# Modu_control_revD.net
KiCad netlist of a schematic drawn in EAGLE
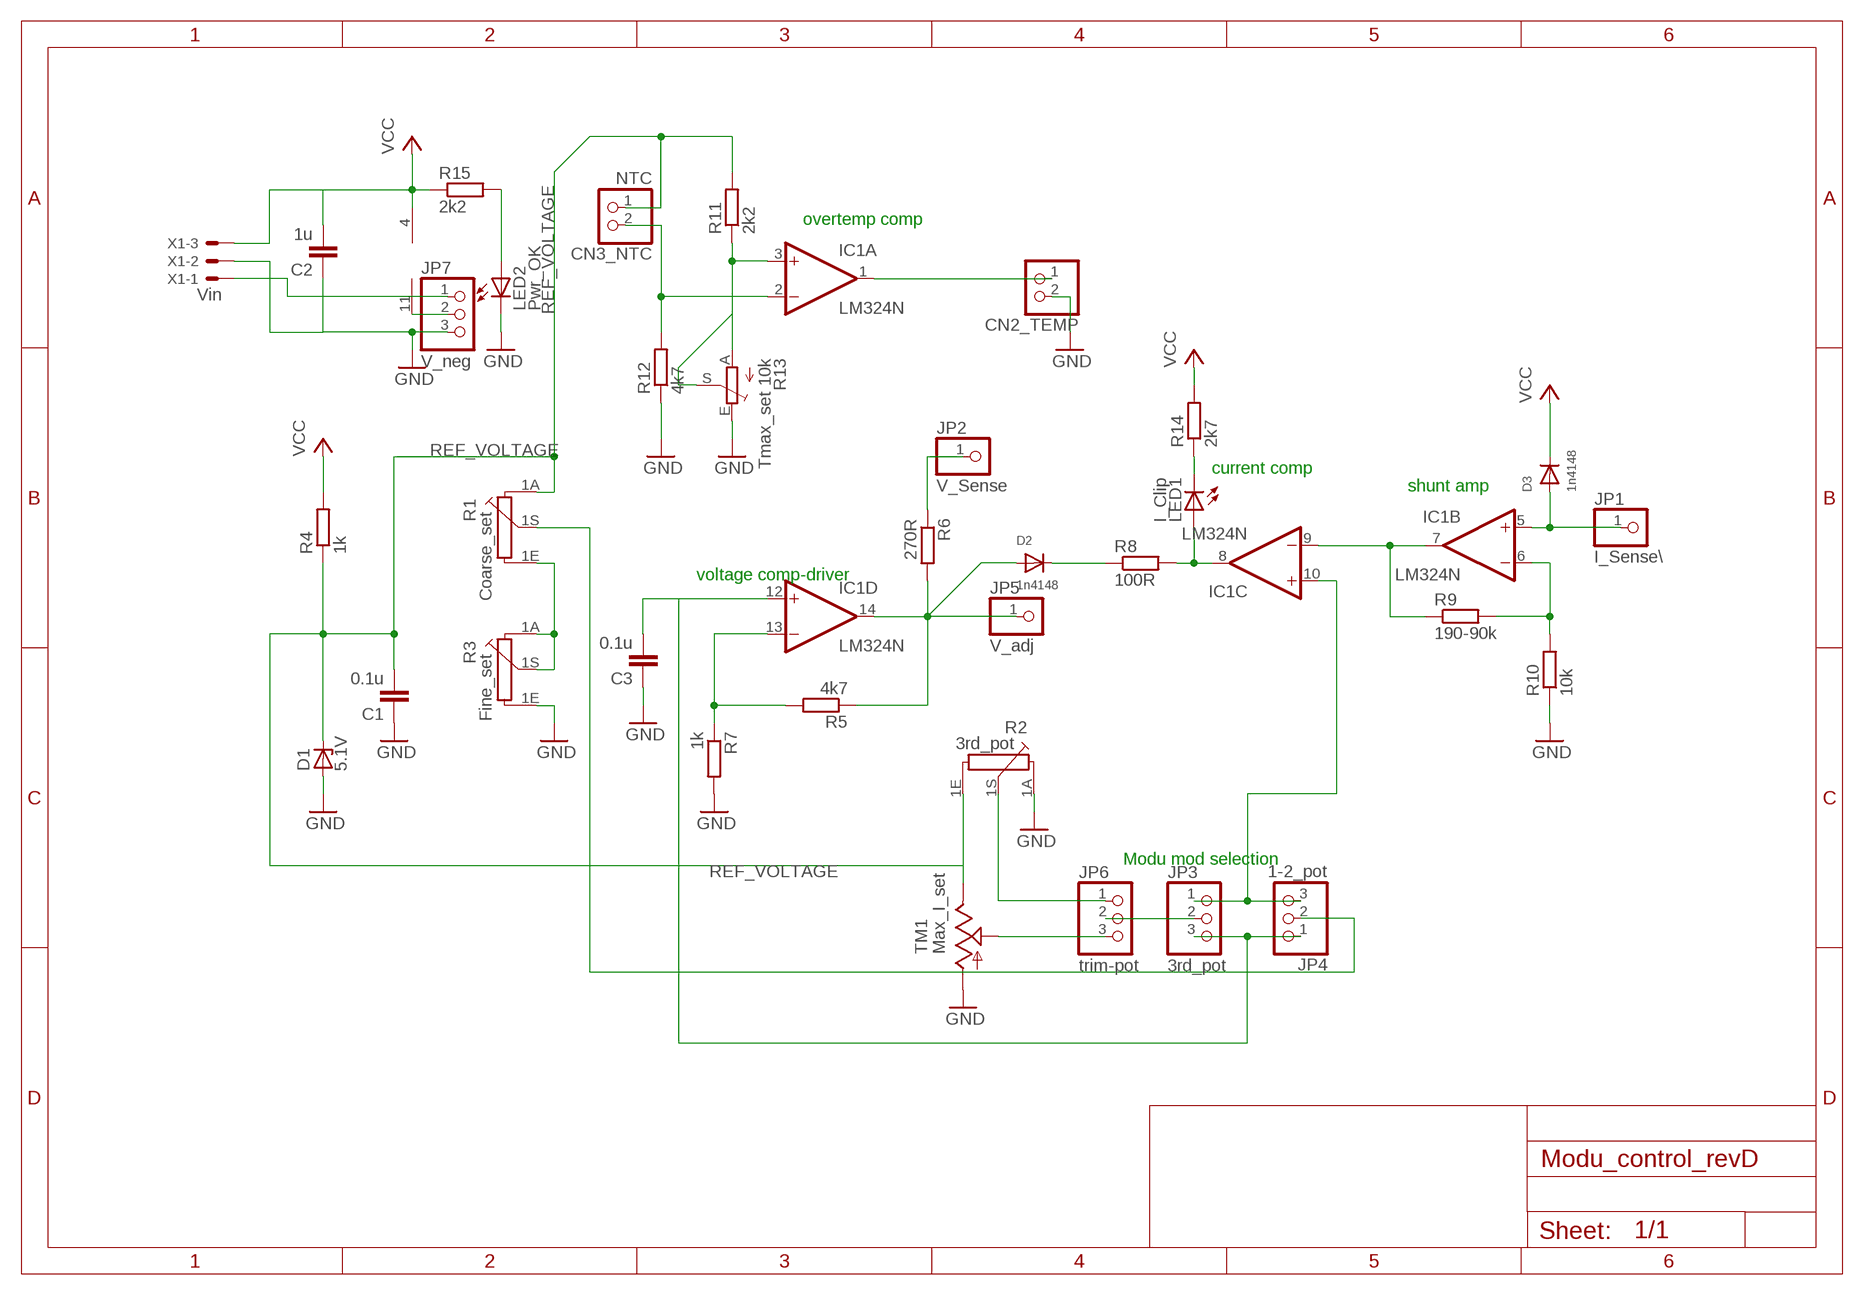
[diagram p0: schematic, sheet 1]

(export (version "E")
  (design (tool "Eeschema 10.0.6"))
  (components
    (comp (ref "C1")
      (value "0.1u")
      (footprint "eagle-import:C050-025X075")
      (libsource (lib "eagle-import") (part "C-EU050-025X075"))
    )
    (comp (ref "C2")
      (value "1u")
      (footprint "eagle-import:C050-025X075")
      (libsource (lib "eagle-import") (part "C-EU050-025X075"))
    )
    (comp (ref "C3")
      (value "0.1u")
      (footprint "eagle-import:C050-025X075")
      (libsource (lib "eagle-import") (part "C-EU050-025X075"))
    )
    (comp (ref "CN2_TEMP")
      (value "JST_2PIN-THM")
      (footprint "eagle-import:JST-PH-2-THM")
      (libsource (lib "eagle-import") (part "JST_2PIN-THM"))
    )
    (comp (ref "CN3_NTC")
      (value "NTC")
      (footprint "eagle-import:JST-PH-2-THM")
      (libsource (lib "eagle-import") (part "JST_2PIN-THM"))
    )
    (comp (ref "D1")
      (value "5.1V")
      (footprint "eagle-import:DO35Z10")
      (libsource (lib "eagle-import") (part "ZENER-DIODEDO35Z10"))
    )
    (comp (ref "D2")
      (value "1n4148")
      (footprint "eagle-import:DO-1N4148")
      (libsource (lib "eagle-import") (part "DIODEDO-1N4148"))
    )
    (comp (ref "D3")
      (value "1n4148")
      (footprint "eagle-import:DO-1N4148")
      (libsource (lib "eagle-import") (part "DIODEDO-1N4148"))
    )
    (comp (ref "IC1")
      (value "LM324N")
      (footprint "eagle-import:DIL14")
      (libsource (lib "eagle-import") (part "LM324N"))
    )
    (comp (ref "JP1")
      (value "I_Sense\\")
      (footprint "eagle-import:1X01")
      (libsource (lib "eagle-import") (part "PINHD-1X1"))
    )
    (comp (ref "JP2")
      (value "V_Sense")
      (footprint "eagle-import:1X01")
      (libsource (lib "eagle-import") (part "PINHD-1X1"))
    )
    (comp (ref "JP3")
      (value "3rd_pot")
      (footprint "eagle-import:1X03")
      (libsource (lib "eagle-import") (part "PINHD-1X3"))
    )
    (comp (ref "JP4")
      (value "1-2_pot")
      (footprint "eagle-import:1X03")
      (libsource (lib "eagle-import") (part "PINHD-1X3"))
    )
    (comp (ref "JP5")
      (value "V_adj")
      (footprint "eagle-import:1X01")
      (libsource (lib "eagle-import") (part "PINHD-1X1"))
    )
    (comp (ref "JP6")
      (value "trim-pot")
      (footprint "eagle-import:1X03")
      (libsource (lib "eagle-import") (part "PINHD-1X3"))
    )
    (comp (ref "JP7")
      (value "V_neg")
      (footprint "eagle-import:1X03")
      (libsource (lib "eagle-import") (part "PINHD-1X3"))
    )
    (comp (ref "LED1")
      (value "I_Clip")
      (footprint "eagle-import:LED3MM")
      (libsource (lib "eagle-import") (part "LED3MM"))
    )
    (comp (ref "LED2")
      (value "Pwr_OK")
      (footprint "eagle-import:LED3MM")
      (libsource (lib "eagle-import") (part "LED3MM"))
    )
    (comp (ref "R1")
      (value "Coarse_set")
      (footprint "eagle-import:PC16S")
      (libsource (lib "eagle-import") (part "PC16S"))
    )
    (comp (ref "R2")
      (value "3rd_pot")
      (footprint "eagle-import:PC16S")
      (libsource (lib "eagle-import") (part "PC16S"))
    )
    (comp (ref "R3")
      (value "Fine_set")
      (footprint "eagle-import:PC16S")
      (libsource (lib "eagle-import") (part "PC16S"))
    )
    (comp (ref "R4")
      (value "1k")
      (footprint "eagle-import:0207_10")
      (libsource (lib "eagle-import") (part "R-EU_0207/10"))
    )
    (comp (ref "R5")
      (value "4k7")
      (footprint "eagle-import:0204V")
      (libsource (lib "eagle-import") (part "R-EU_0204/2V"))
    )
    (comp (ref "R6")
      (value "270R")
      (footprint "eagle-import:0204V")
      (libsource (lib "eagle-import") (part "R-EU_0204/2V"))
    )
    (comp (ref "R7")
      (value "1k")
      (footprint "eagle-import:0204_7")
      (libsource (lib "eagle-import") (part "R-EU_0204/7"))
    )
    (comp (ref "R8")
      (value "100R")
      (footprint "eagle-import:0204V")
      (libsource (lib "eagle-import") (part "R-EU_0204/2V"))
    )
    (comp (ref "R9")
      (value "190-90k")
      (footprint "eagle-import:0204V")
      (libsource (lib "eagle-import") (part "R-EU_0204/2V"))
    )
    (comp (ref "R10")
      (value "10k")
      (footprint "eagle-import:0204_7")
      (libsource (lib "eagle-import") (part "R-EU_0204/7"))
    )
    (comp (ref "R11")
      (value "2k2")
      (footprint "eagle-import:0204_7")
      (libsource (lib "eagle-import") (part "R-EU_0204/7"))
    )
    (comp (ref "R12")
      (value "4k7")
      (footprint "eagle-import:0204V")
      (libsource (lib "eagle-import") (part "R-EU_0204/2V"))
    )
    (comp (ref "R13")
      (value "Tmax_set 10k")
      (footprint "eagle-import:B25P")
      (libsource (lib "eagle-import") (part "TRIM_EU-B25P"))
    )
    (comp (ref "R14")
      (value "2k7")
      (footprint "eagle-import:0204V")
      (libsource (lib "eagle-import") (part "R-EU_0204/2V"))
    )
    (comp (ref "R15")
      (value "2k2")
      (footprint "eagle-import:0204V")
      (libsource (lib "eagle-import") (part "R-EU_0204/2V"))
    )
    (comp (ref "TM1")
      (value "Max_I_set")
      (footprint "eagle-import:6MM")
      (libsource (lib "eagle-import") (part "TRIM"))
    )
    (comp (ref "X1")
      (value "Vin")
      (footprint "eagle-import:JST-XH-03-PACKAGE-LONG-PAD")
      (libsource (lib "eagle-import") (part "JST-XH-03-PIN-LONG-PAD"))
    )
  )
  (nets
    (net (code "1") (name "/REF_VOLTAGE") (class "Default")
      (node (ref "C1") (pin "2") (pinfunction "2_2") (pintype "passive"))
      (node (ref "CN3_NTC") (pin "1") (pinfunction "2_1") (pintype "passive"))
      (node (ref "D1") (pin "C") (pinfunction "C_C") (pintype "passive"))
      (node (ref "R1") (pin "1A") (pinfunction "1A_1A") (pintype "passive"))
      (node (ref "R11") (pin "2") (pinfunction "2_2") (pintype "passive"))
      (node (ref "R2") (pin "1E") (pinfunction "1E_1E") (pintype "passive"))
      (node (ref "R4") (pin "1") (pinfunction "1_1") (pintype "passive"))
      (node (ref "TM1") (pin "E") (pinfunction "E_E") (pintype "passive"))
    )
    (net (code "2") (name "GND") (class "Default")
      (node (ref "C1") (pin "1") (pinfunction "1_1") (pintype "passive"))
      (node (ref "C2") (pin "1") (pinfunction "1_1") (pintype "passive"))
      (node (ref "C3") (pin "1") (pinfunction "1_1") (pintype "passive"))
      (node (ref "CN2_TEMP") (pin "2") (pinfunction "1_2") (pintype "passive"))
      (node (ref "D1") (pin "A") (pinfunction "A_A") (pintype "passive"))
      (node (ref "JP7") (pin "3") (pinfunction "3_3") (pintype "passive"))
      (node (ref "LED2") (pin "K") (pinfunction "C_K") (pintype "passive"))
      (node (ref "R10") (pin "1") (pinfunction "1_1") (pintype "passive"))
      (node (ref "R12") (pin "1") (pinfunction "1_1") (pintype "passive"))
      (node (ref "R13") (pin "E") (pinfunction "E_E") (pintype "passive"))
      (node (ref "R2") (pin "1A") (pinfunction "1A_1A") (pintype "passive"))
      (node (ref "R3") (pin "1E") (pinfunction "1E_1E") (pintype "passive"))
      (node (ref "R7") (pin "2") (pinfunction "2_2") (pintype "passive"))
      (node (ref "TM1") (pin "A") (pinfunction "A_A") (pintype "passive"))
      (node (ref "X1") (pin "2") (pinfunction "S_2") (pintype "passive"))
    )
    (net (code "3") (name "Net-(CN2_TEMP-2)") (class "Default")
      (node (ref "CN2_TEMP") (pin "1") (pinfunction "2_1") (pintype "passive"))
      (node (ref "IC1") (pin "1") (pinfunction "OUT_1") (pintype "output"))
    )
    (net (code "4") (name "Net-(CN3_NTC-1)") (class "Default")
      (node (ref "CN3_NTC") (pin "2") (pinfunction "1_2") (pintype "passive"))
      (node (ref "IC1") (pin "2") (pinfunction "-IN_2") (pintype "input"))
      (node (ref "R12") (pin "2") (pinfunction "2_2") (pintype "passive"))
    )
    (net (code "5") (name "Net-(D2-PadC)") (class "Default")
      (node (ref "D2") (pin "C") (pinfunction "C_C") (pintype "passive"))
      (node (ref "R8") (pin "1") (pinfunction "1_1") (pintype "passive"))
    )
    (net (code "6") (name "Net-(IC1A-+IN)") (class "Default")
      (node (ref "IC1") (pin "3") (pinfunction "+IN_3") (pintype "input"))
      (node (ref "R11") (pin "1") (pinfunction "1_1") (pintype "passive"))
      (node (ref "R13") (pin "A") (pinfunction "A_A") (pintype "passive"))
      (node (ref "R13") (pin "S") (pinfunction "S_S") (pintype "passive"))
    )
    (net (code "7") (name "Net-(IC1B-+IN)") (class "Default")
      (node (ref "D3") (pin "A") (pinfunction "A_A") (pintype "passive"))
      (node (ref "IC1") (pin "5") (pinfunction "+IN_5") (pintype "input"))
      (node (ref "JP1") (pin "1") (pinfunction "1_1") (pintype "passive"))
    )
    (net (code "8") (name "Net-(IC1B--IN)") (class "Default")
      (node (ref "IC1") (pin "6") (pinfunction "-IN_6") (pintype "input"))
      (node (ref "R10") (pin "2") (pinfunction "2_2") (pintype "passive"))
      (node (ref "R9") (pin "2") (pinfunction "2_2") (pintype "passive"))
    )
    (net (code "9") (name "Net-(IC1B-OUT)") (class "Default")
      (node (ref "IC1") (pin "7") (pinfunction "OUT_7") (pintype "output"))
      (node (ref "IC1") (pin "9") (pinfunction "-IN_9") (pintype "input"))
      (node (ref "R9") (pin "1") (pinfunction "1_1") (pintype "passive"))
    )
    (net (code "10") (name "Net-(IC1C-+IN)") (class "Default")
      (node (ref "IC1") (pin "10") (pinfunction "+IN_10") (pintype "input"))
      (node (ref "JP3") (pin "1") (pinfunction "1_1") (pintype "passive"))
      (node (ref "JP4") (pin "3") (pinfunction "3_3") (pintype "passive"))
    )
    (net (code "11") (name "Net-(IC1C-OUT)") (class "Default")
      (node (ref "IC1") (pin "8") (pinfunction "OUT_8") (pintype "output"))
      (node (ref "LED1") (pin "A") (pinfunction "A_A") (pintype "passive"))
      (node (ref "R8") (pin "2") (pinfunction "2_2") (pintype "passive"))
    )
    (net (code "12") (name "Net-(IC1D-+IN)") (class "Default")
      (node (ref "C3") (pin "2") (pinfunction "2_2") (pintype "passive"))
      (node (ref "IC1") (pin "12") (pinfunction "+IN_12") (pintype "input"))
      (node (ref "JP3") (pin "3") (pinfunction "3_3") (pintype "passive"))
      (node (ref "JP4") (pin "1") (pinfunction "1_1") (pintype "passive"))
    )
    (net (code "13") (name "Net-(IC1D--IN)") (class "Default")
      (node (ref "IC1") (pin "13") (pinfunction "-IN_13") (pintype "input"))
      (node (ref "R5") (pin "2") (pinfunction "2_2") (pintype "passive"))
      (node (ref "R7") (pin "1") (pinfunction "1_1") (pintype "passive"))
    )
    (net (code "14") (name "Net-(IC1D-OUT)") (class "Default")
      (node (ref "D2") (pin "A") (pinfunction "A_A") (pintype "passive"))
      (node (ref "IC1") (pin "14") (pinfunction "OUT_14") (pintype "output"))
      (node (ref "JP5") (pin "1") (pinfunction "1_1") (pintype "passive"))
      (node (ref "R5") (pin "1") (pinfunction "1_1") (pintype "passive"))
      (node (ref "R6") (pin "2") (pinfunction "2_2") (pintype "passive"))
    )
    (net (code "15") (name "Net-(IC1E-V-)") (class "Default")
      (node (ref "IC1") (pin "11") (pinfunction "V-_11") (pintype "power_in"))
      (node (ref "JP7") (pin "2") (pinfunction "2_2") (pintype "passive"))
    )
    (net (code "16") (name "Net-(JP2-Pad1)") (class "Default")
      (node (ref "JP2") (pin "1") (pinfunction "1_1") (pintype "passive"))
      (node (ref "R6") (pin "1") (pinfunction "1_1") (pintype "passive"))
    )
    (net (code "17") (name "Net-(JP3-Pad2)") (class "Default")
      (node (ref "JP3") (pin "2") (pinfunction "2_2") (pintype "passive"))
      (node (ref "JP6") (pin "2") (pinfunction "2_2") (pintype "passive"))
    )
    (net (code "18") (name "Net-(JP4-Pad2)") (class "Default")
      (node (ref "JP4") (pin "2") (pinfunction "2_2") (pintype "passive"))
      (node (ref "R1") (pin "1S") (pinfunction "1S_1S") (pintype "passive"))
    )
    (net (code "19") (name "Net-(JP6-Pad1)") (class "Default")
      (node (ref "JP6") (pin "1") (pinfunction "1_1") (pintype "passive"))
      (node (ref "R2") (pin "1S") (pinfunction "1S_1S") (pintype "passive"))
    )
    (net (code "20") (name "Net-(JP6-Pad3)") (class "Default")
      (node (ref "JP6") (pin "3") (pinfunction "3_3") (pintype "passive"))
      (node (ref "TM1") (pin "S") (pinfunction "S_S") (pintype "passive"))
    )
    (net (code "21") (name "Net-(LED1-C)") (class "Default")
      (node (ref "LED1") (pin "K") (pinfunction "C_K") (pintype "passive"))
      (node (ref "R14") (pin "1") (pinfunction "1_1") (pintype "passive"))
    )
    (net (code "22") (name "Net-(LED2-PadA)") (class "Default")
      (node (ref "LED2") (pin "A") (pinfunction "A_A") (pintype "passive"))
      (node (ref "R15") (pin "2") (pinfunction "2_2") (pintype "passive"))
    )
    (net (code "23") (name "Net-(R1-Pad1E)") (class "Default")
      (node (ref "R1") (pin "1E") (pinfunction "1E_1E") (pintype "passive"))
      (node (ref "R3") (pin "1A") (pinfunction "1A_1A") (pintype "passive"))
      (node (ref "R3") (pin "1S") (pinfunction "1S_1S") (pintype "passive"))
    )
    (net (code "24") (name "Net-(X1A-S)") (class "Default")
      (node (ref "JP7") (pin "1") (pinfunction "1_1") (pintype "passive"))
      (node (ref "X1") (pin "1") (pinfunction "S_1") (pintype "passive"))
    )
    (net (code "25") (name "VCC") (class "Default")
      (node (ref "C2") (pin "2") (pinfunction "2_2") (pintype "passive"))
      (node (ref "D3") (pin "C") (pinfunction "C_C") (pintype "passive"))
      (node (ref "IC1") (pin "4") (pinfunction "V+_4") (pintype "power_in"))
      (node (ref "R14") (pin "2") (pinfunction "2_2") (pintype "passive"))
      (node (ref "R15") (pin "1") (pinfunction "1_1") (pintype "passive"))
      (node (ref "R4") (pin "2") (pinfunction "2_2") (pintype "passive"))
      (node (ref "X1") (pin "3") (pinfunction "S_3") (pintype "passive"))
    )
  )
)
